# Z2T.net
KiCad netlist of a schematic drawn in EAGLE
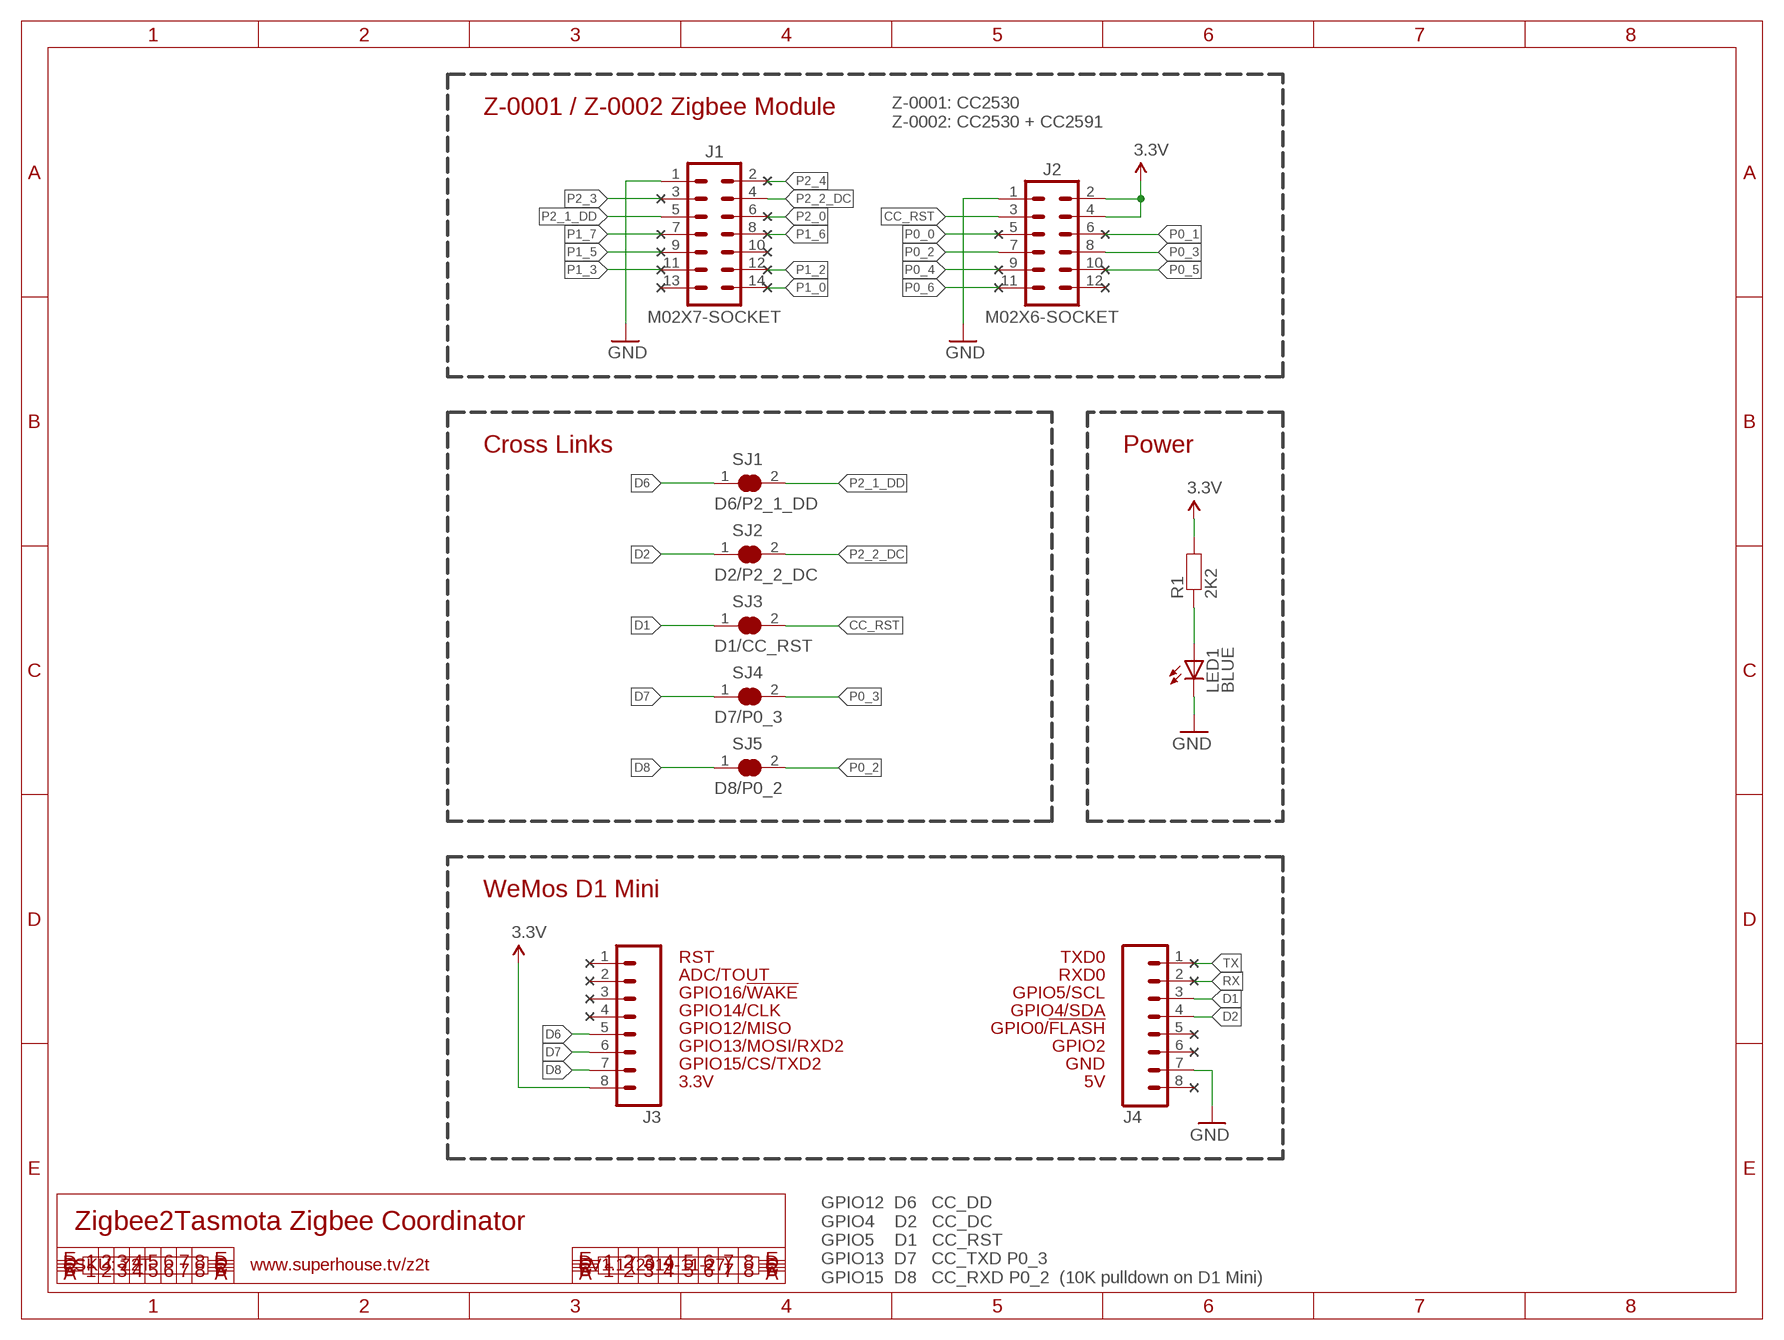
[diagram p0: schematic, sheet 1]

(export (version "E")
  (design (tool "Eeschema 10.0.6"))
  (components
    (comp (ref "J1")
      (value "M02X7-SOCKET")
      (footprint "eagle-import:2X07-S")
      (libsource (lib "eagle-import") (part "M02X7-SOCKET"))
    )
    (comp (ref "J2")
      (value "M02X6-SOCKET")
      (footprint "eagle-import:2X06-S")
      (libsource (lib "eagle-import") (part "M02X6-SOCKET"))
    )
    (comp (ref "J3")
      (value "M08")
      (footprint "eagle-import:1X08")
      (libsource (lib "eagle-import") (part "M08"))
    )
    (comp (ref "J4")
      (value "M08")
      (footprint "eagle-import:1X08")
      (libsource (lib "eagle-import") (part "M08"))
    )
    (comp (ref "LED1")
      (value "BLUE")
      (footprint "eagle-import:LED-0603")
      (libsource (lib "eagle-import") (part "LED0603"))
    )
    (comp (ref "R1")
      (value "2K2")
      (footprint "eagle-import:R0603")
      (libsource (lib "eagle-import") (part "RESISTOR0603"))
    )
    (comp (ref "SJ1")
      (value "D6/P2_1_DD")
      (footprint "eagle-import:SJC")
      (libsource (lib "eagle-import") (part "SJC-NORMAL"))
    )
    (comp (ref "SJ2")
      (value "D2/P2_2_DC")
      (footprint "eagle-import:SJC")
      (libsource (lib "eagle-import") (part "SJC-NORMAL"))
    )
    (comp (ref "SJ3")
      (value "D1/CC_RST")
      (footprint "eagle-import:SJC")
      (libsource (lib "eagle-import") (part "SJC-NORMAL"))
    )
    (comp (ref "SJ4")
      (value "D7/P0_3")
      (footprint "eagle-import:SJC")
      (libsource (lib "eagle-import") (part "SJC-NORMAL"))
    )
    (comp (ref "SJ5")
      (value "D8/P0_2")
      (footprint "eagle-import:SJC")
      (libsource (lib "eagle-import") (part "SJC-NORMAL"))
    )
  )
  (nets
    (net (code "1") (name "3.3V") (class "Default")
      (node (ref "J2") (pin "2") (pinfunction "2_2") (pintype "passive"))
      (node (ref "J2") (pin "4") (pinfunction "4_4") (pintype "passive"))
      (node (ref "J3") (pin "8") (pinfunction "8_8") (pintype "passive"))
      (node (ref "R1") (pin "2") (pinfunction "2_2") (pintype "passive"))
    )
    (net (code "2") (name "CC_RST") (class "Default")
      (node (ref "J2") (pin "3") (pinfunction "3_3") (pintype "passive"))
      (node (ref "SJ3") (pin "2") (pinfunction "2_2") (pintype "passive"))
    )
    (net (code "3") (name "D1") (class "Default")
      (node (ref "J4") (pin "3") (pinfunction "3_3") (pintype "passive"))
      (node (ref "SJ3") (pin "1") (pinfunction "1_1") (pintype "passive"))
    )
    (net (code "4") (name "D2") (class "Default")
      (node (ref "J4") (pin "4") (pinfunction "4_4") (pintype "passive"))
      (node (ref "SJ2") (pin "1") (pinfunction "1_1") (pintype "passive"))
    )
    (net (code "5") (name "D6") (class "Default")
      (node (ref "J3") (pin "5") (pinfunction "5_5") (pintype "passive"))
      (node (ref "SJ1") (pin "1") (pinfunction "1_1") (pintype "passive"))
    )
    (net (code "6") (name "D7") (class "Default")
      (node (ref "J3") (pin "6") (pinfunction "6_6") (pintype "passive"))
      (node (ref "SJ4") (pin "1") (pinfunction "1_1") (pintype "passive"))
    )
    (net (code "7") (name "D8") (class "Default")
      (node (ref "J3") (pin "7") (pinfunction "7_7") (pintype "passive"))
      (node (ref "SJ5") (pin "1") (pinfunction "1_1") (pintype "passive"))
    )
    (net (code "8") (name "GND") (class "Default")
      (node (ref "J1") (pin "1") (pinfunction "1_1") (pintype "passive"))
      (node (ref "J2") (pin "1") (pinfunction "1_1") (pintype "passive"))
      (node (ref "J4") (pin "7") (pinfunction "7_7") (pintype "passive"))
      (node (ref "LED1") (pin "C") (pinfunction "C_C") (pintype "passive"))
    )
    (net (code "9") (name "Net-(LED1-PadA)") (class "Default")
      (node (ref "LED1") (pin "A") (pinfunction "A_A") (pintype "passive"))
      (node (ref "R1") (pin "1") (pinfunction "1_1") (pintype "passive"))
    )
    (net (code "10") (name "P0_0") (class "Default")
      (node (ref "J2") (pin "5") (pinfunction "5_5") (pintype "passive"))
    )
    (net (code "11") (name "P0_1") (class "Default")
      (node (ref "J2") (pin "6") (pinfunction "6_6") (pintype "passive"))
    )
    (net (code "12") (name "P0_2") (class "Default")
      (node (ref "J2") (pin "7") (pinfunction "7_7") (pintype "passive"))
      (node (ref "SJ5") (pin "2") (pinfunction "2_2") (pintype "passive"))
    )
    (net (code "13") (name "P0_3") (class "Default")
      (node (ref "J2") (pin "8") (pinfunction "8_8") (pintype "passive"))
      (node (ref "SJ4") (pin "2") (pinfunction "2_2") (pintype "passive"))
    )
    (net (code "14") (name "P0_4") (class "Default")
      (node (ref "J2") (pin "9") (pinfunction "9_9") (pintype "passive"))
    )
    (net (code "15") (name "P0_5") (class "Default")
      (node (ref "J2") (pin "10") (pinfunction "10_10") (pintype "passive"))
    )
    (net (code "16") (name "P0_6") (class "Default")
      (node (ref "J2") (pin "11") (pinfunction "11_11") (pintype "passive"))
    )
    (net (code "17") (name "P1_0") (class "Default")
      (node (ref "J1") (pin "14") (pinfunction "14_14") (pintype "passive"))
    )
    (net (code "18") (name "P1_2") (class "Default")
      (node (ref "J1") (pin "12") (pinfunction "12_12") (pintype "passive"))
    )
    (net (code "19") (name "P1_3") (class "Default")
      (node (ref "J1") (pin "11") (pinfunction "11_11") (pintype "passive"))
    )
    (net (code "20") (name "P1_5") (class "Default")
      (node (ref "J1") (pin "9") (pinfunction "9_9") (pintype "passive"))
    )
    (net (code "21") (name "P1_6") (class "Default")
      (node (ref "J1") (pin "8") (pinfunction "8_8") (pintype "passive"))
    )
    (net (code "22") (name "P1_7") (class "Default")
      (node (ref "J1") (pin "7") (pinfunction "7_7") (pintype "passive"))
    )
    (net (code "23") (name "P2_0") (class "Default")
      (node (ref "J1") (pin "6") (pinfunction "6_6") (pintype "passive"))
    )
    (net (code "24") (name "P2_1_DD") (class "Default")
      (node (ref "J1") (pin "5") (pinfunction "5_5") (pintype "passive"))
      (node (ref "SJ1") (pin "2") (pinfunction "2_2") (pintype "passive"))
    )
    (net (code "25") (name "P2_2_DC") (class "Default")
      (node (ref "J1") (pin "4") (pinfunction "4_4") (pintype "passive"))
      (node (ref "SJ2") (pin "2") (pinfunction "2_2") (pintype "passive"))
    )
    (net (code "26") (name "P2_3") (class "Default")
      (node (ref "J1") (pin "3") (pinfunction "3_3") (pintype "passive"))
    )
    (net (code "27") (name "P2_4") (class "Default")
      (node (ref "J1") (pin "2") (pinfunction "2_2") (pintype "passive"))
    )
    (net (code "28") (name "RX") (class "Default")
      (node (ref "J4") (pin "2") (pinfunction "2_2") (pintype "passive"))
    )
    (net (code "29") (name "TX") (class "Default")
      (node (ref "J4") (pin "1") (pinfunction "1_1") (pintype "passive"))
    )
    (net (code "30") (name "unconnected-(J1-Pad10)") (class "Default")
      (node (ref "J1") (pin "10") (pinfunction "10_10") (pintype "passive"))
    )
    (net (code "31") (name "unconnected-(J1-Pad13)") (class "Default")
      (node (ref "J1") (pin "13") (pinfunction "13_13") (pintype "passive"))
    )
    (net (code "32") (name "unconnected-(J2-Pad12)") (class "Default")
      (node (ref "J2") (pin "12") (pinfunction "12_12") (pintype "passive"))
    )
    (net (code "33") (name "unconnected-(J3-Pad1)") (class "Default")
      (node (ref "J3") (pin "1") (pinfunction "1_1") (pintype "passive"))
    )
    (net (code "34") (name "unconnected-(J3-Pad2)") (class "Default")
      (node (ref "J3") (pin "2") (pinfunction "2_2") (pintype "passive"))
    )
    (net (code "35") (name "unconnected-(J3-Pad3)") (class "Default")
      (node (ref "J3") (pin "3") (pinfunction "3_3") (pintype "passive"))
    )
    (net (code "36") (name "unconnected-(J3-Pad4)") (class "Default")
      (node (ref "J3") (pin "4") (pinfunction "4_4") (pintype "passive"))
    )
    (net (code "37") (name "unconnected-(J4-Pad5)") (class "Default")
      (node (ref "J4") (pin "5") (pinfunction "5_5") (pintype "passive"))
    )
    (net (code "38") (name "unconnected-(J4-Pad6)") (class "Default")
      (node (ref "J4") (pin "6") (pinfunction "6_6") (pintype "passive"))
    )
    (net (code "39") (name "unconnected-(J4-Pad8)") (class "Default")
      (node (ref "J4") (pin "8") (pinfunction "8_8") (pintype "passive"))
    )
  )
)
